# HC-NBIOT_Single_lamp_controller-V1_1.net
KiCad netlist of a schematic drawn in Altium Designer
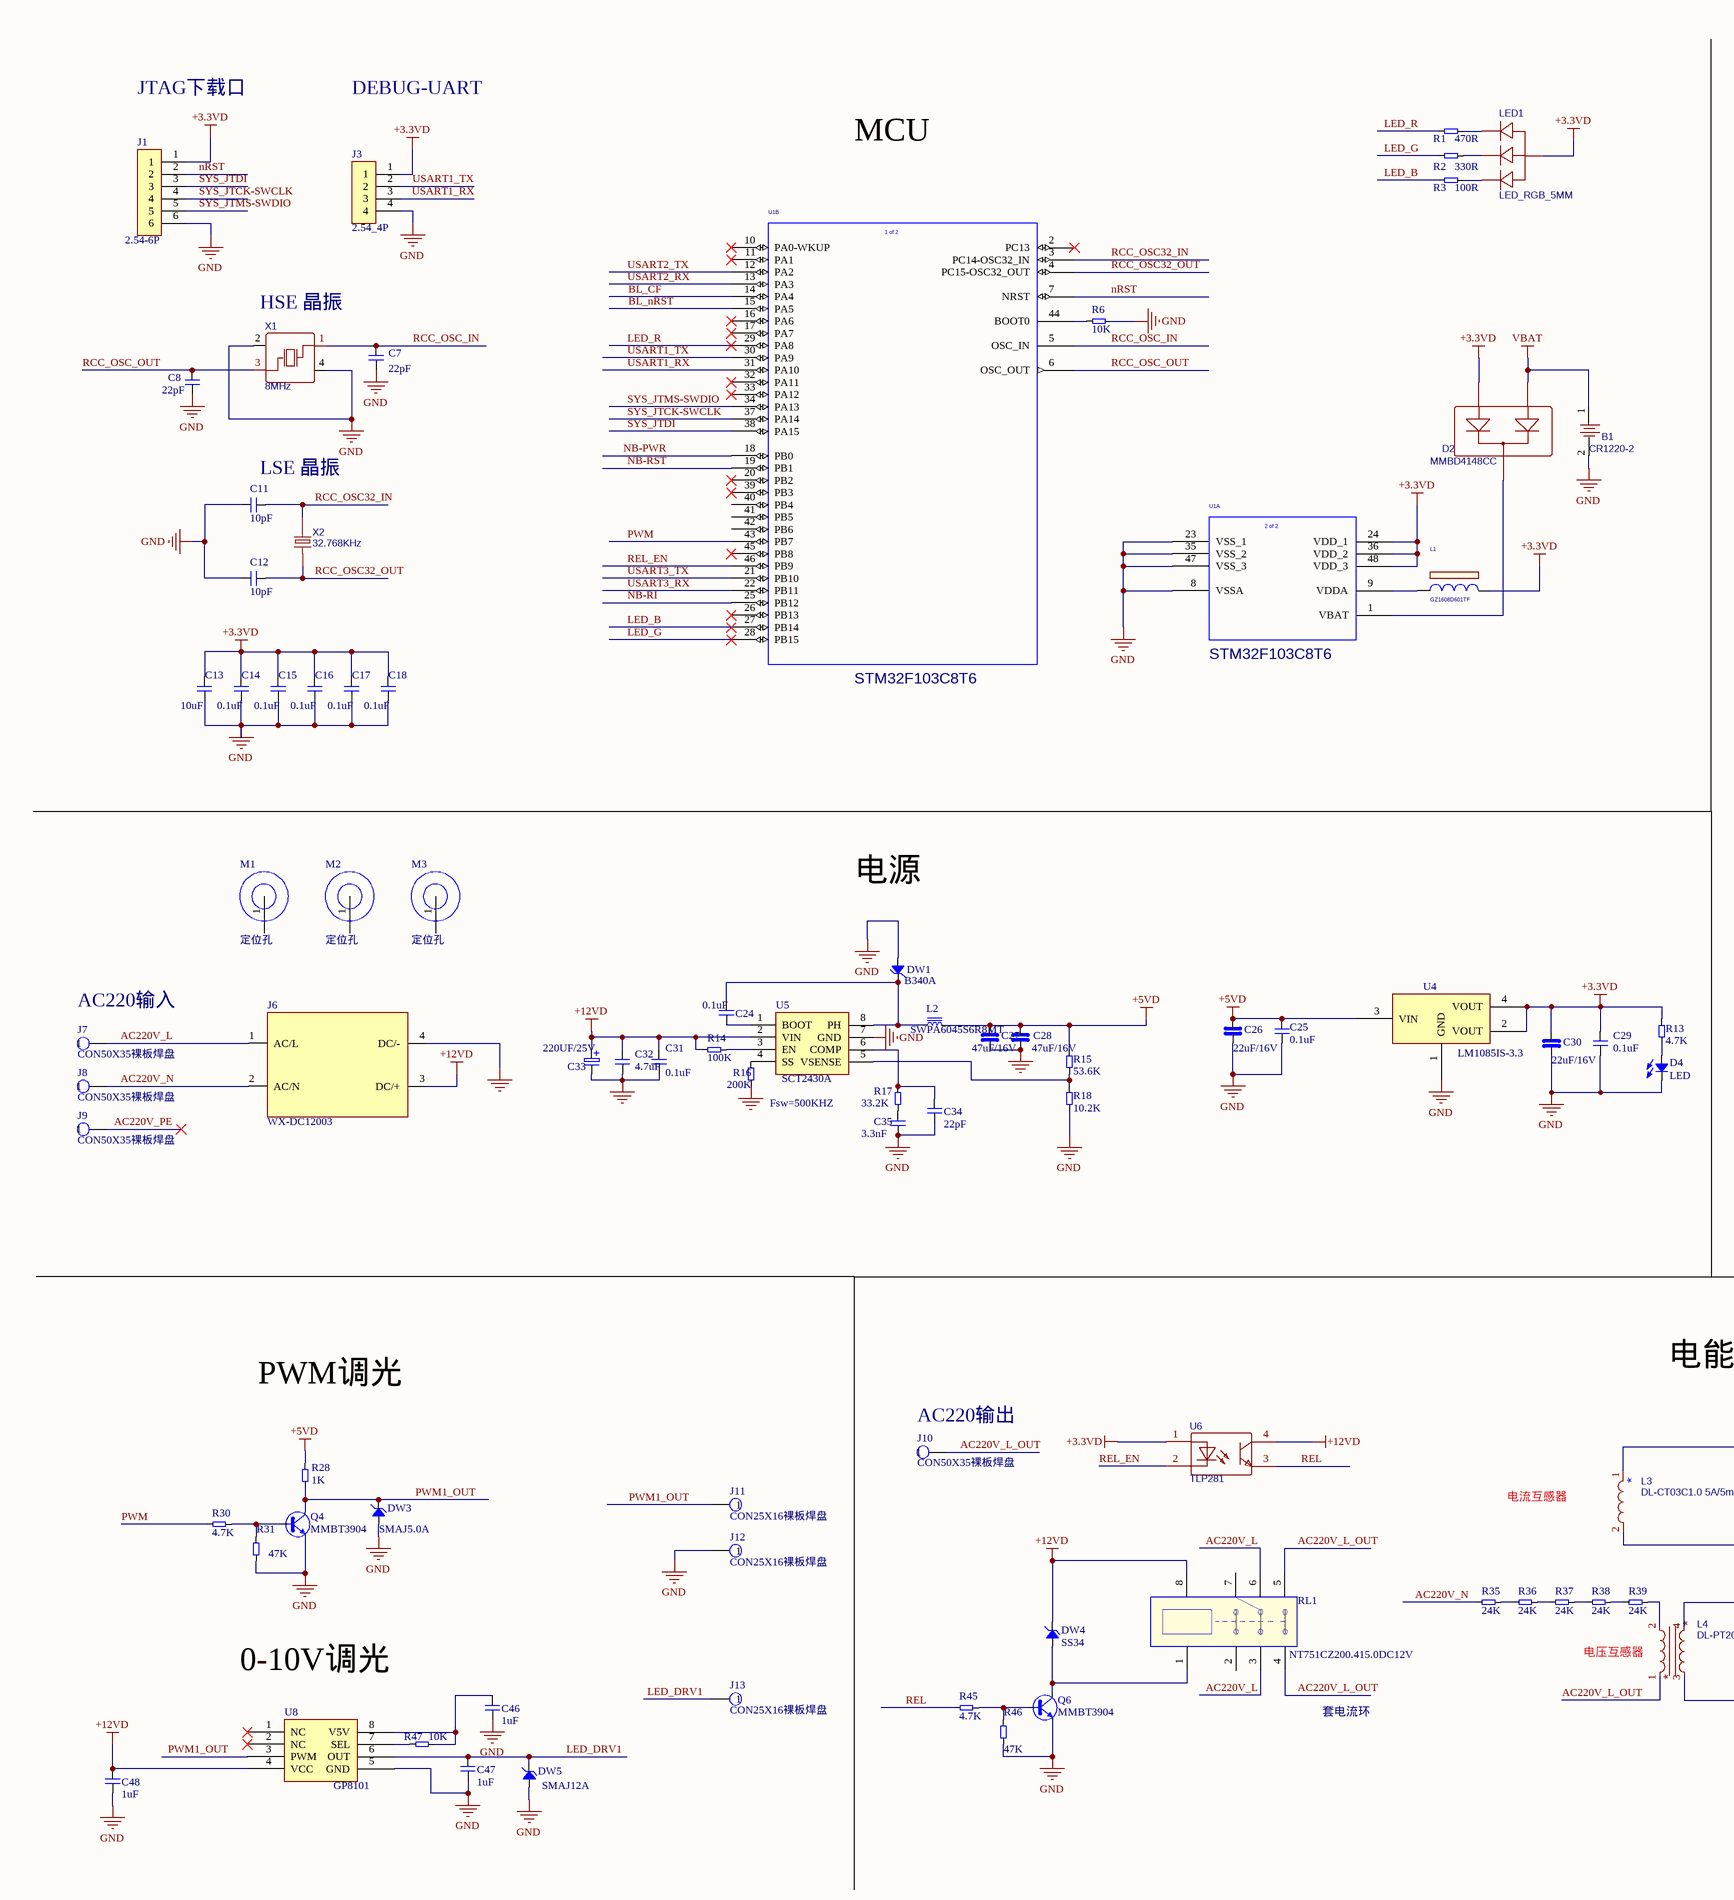
[diagram p0: HC-NBIOT_Single_lamp_controller-V1.1.SchDoc, left]
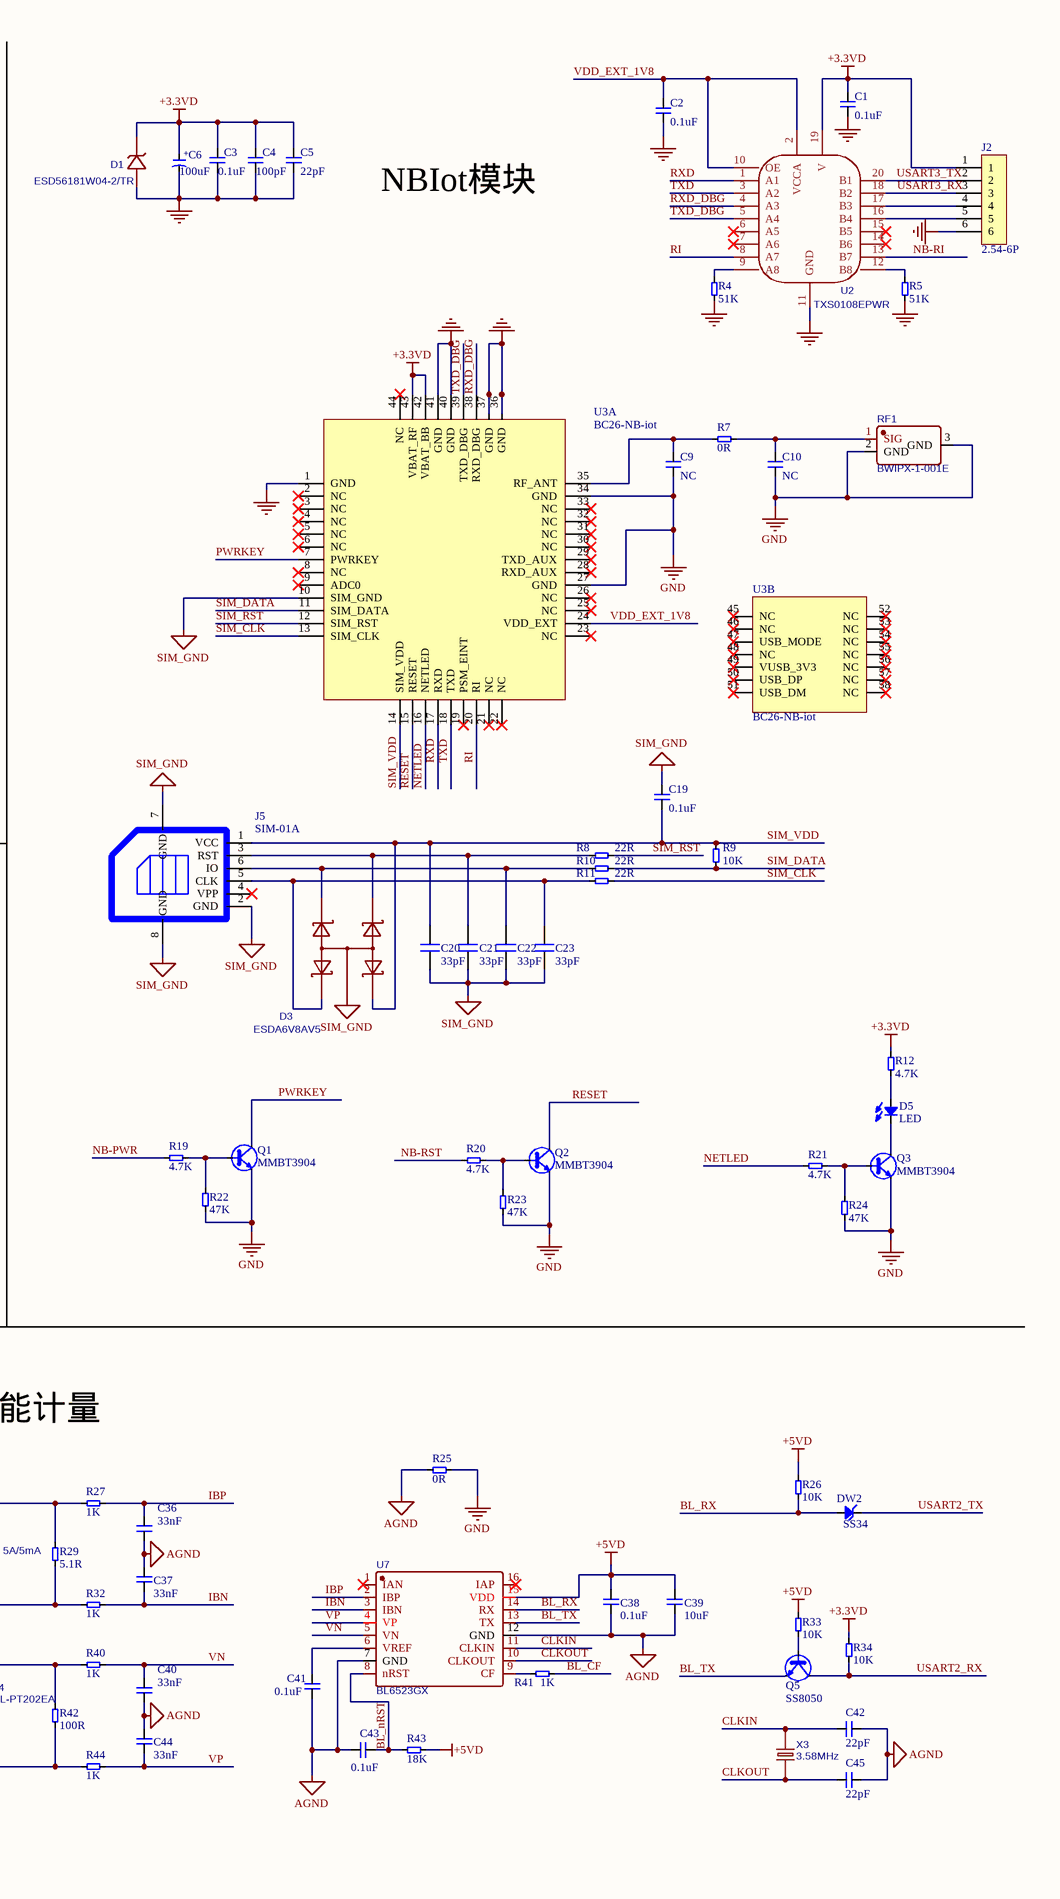
[diagram p1: HC-NBIOT_Single_lamp_controller-V1.1.SchDoc, right]

(export (version "E")
  (design (tool "Eeschema 10.0.6"))
  (components
    (comp (ref "B1")
      (value "CR1220-2")
      (footprint "BAT-SMD_CR1220-2")
      (fields (field (name "BOM_SUPPLIER PART") "C70381"))
      (libsource (lib "czc") (part "CR1220-2"))
    )
    (comp (ref "C1")
      (value "0.1uF")
      (footprint "0603C")
      (description "电容")
      (libsource (lib "DOFAR_AD_LIB") (part "电容"))
    )
    (comp (ref "C2")
      (value "0.1uF")
      (footprint "0603C")
      (description "电容")
      (libsource (lib "DOFAR_AD_LIB") (part "电容"))
    )
    (comp (ref "C3")
      (value "0.1uF")
      (footprint "0603C")
      (description "电容")
      (libsource (lib "DOFAR_AD_LIB") (part "电容"))
    )
    (comp (ref "C4")
      (value "100pF")
      (footprint "0603C")
      (description "电容")
      (libsource (lib "DOFAR_AD_LIB") (part "电容"))
    )
    (comp (ref "C5")
      (value "22pF")
      (footprint "0603C")
      (description "电容")
      (libsource (lib "DOFAR_AD_LIB") (part "电容"))
    )
    (comp (ref "C6")
      (value "100uF")
      (footprint "CAP-SMD_L3.5-W2.8")
      (description "电解电容")
      (libsource (lib "czc") (part "Capacitor"))
    )
    (comp (ref "C7")
      (value "22pF")
      (footprint "0603C")
      (description "电容")
      (libsource (lib "DOFAR_AD_LIB") (part "电容"))
    )
    (comp (ref "C8")
      (value "22pF")
      (footprint "0603C")
      (description "电容")
      (libsource (lib "DOFAR_AD_LIB") (part "电容"))
    )
    (comp (ref "C9")
      (value "NC")
      (footprint "0603C")
      (description "电容")
      (libsource (lib "DOFAR_AD_LIB") (part "电容"))
    )
    (comp (ref "C10")
      (value "NC")
      (footprint "0603C")
      (description "电容")
      (libsource (lib "DOFAR_AD_LIB") (part "电容"))
    )
    (comp (ref "C11")
      (value "10pF")
      (footprint "0603C")
      (description "电容")
      (libsource (lib "DOFAR_AD_LIB") (part "电容"))
    )
    (comp (ref "C12")
      (value "10pF")
      (footprint "0603C")
      (description "电容")
      (libsource (lib "DOFAR_AD_LIB") (part "电容"))
    )
    (comp (ref "C13")
      (value "10uF")
      (footprint "1206C")
      (description "电容")
      (libsource (lib "DOFAR_AD_LIB") (part "电容"))
    )
    (comp (ref "C14")
      (value "0.1uF")
      (footprint "0603C")
      (description "电容")
      (libsource (lib "DOFAR_AD_LIB") (part "电容"))
    )
    (comp (ref "C15")
      (value "0.1uF")
      (footprint "0603C")
      (description "电容")
      (libsource (lib "DOFAR_AD_LIB") (part "电容"))
    )
    (comp (ref "C16")
      (value "0.1uF")
      (footprint "0603C")
      (description "电容")
      (libsource (lib "DOFAR_AD_LIB") (part "电容"))
    )
    (comp (ref "C17")
      (value "0.1uF")
      (footprint "0603C")
      (description "电容")
      (libsource (lib "DOFAR_AD_LIB") (part "电容"))
    )
    (comp (ref "C18")
      (value "0.1uF")
      (footprint "0603C")
      (description "电容")
      (libsource (lib "DOFAR_AD_LIB") (part "电容"))
    )
    (comp (ref "C19")
      (value "0.1uF")
      (footprint "0603C")
      (description "电容")
      (libsource (lib "DOFAR_AD_LIB") (part "电容"))
    )
    (comp (ref "C20")
      (value "33pF")
      (footprint "0603C")
      (description "电容")
      (libsource (lib "czc") (part "CAP"))
    )
    (comp (ref "C21")
      (value "33pF")
      (footprint "0603C")
      (description "电容")
      (libsource (lib "czc") (part "CAP"))
    )
    (comp (ref "C22")
      (value "33pF")
      (footprint "0603C")
      (description "电容")
      (libsource (lib "czc") (part "CAP"))
    )
    (comp (ref "C23")
      (value "33pF")
      (footprint "0603C")
      (description "电容")
      (libsource (lib "czc") (part "CAP"))
    )
    (comp (ref "C24")
      (value "0.1uF")
      (footprint "0603C")
      (description "电容")
      (libsource (lib "DOFAR_AD_LIB") (part "电容"))
    )
    (comp (ref "C25")
      (value "0.1uF")
      (footprint "0603C")
      (description "电容")
      (libsource (lib "*") (part "电容"))
    )
    (comp (ref "C26")
      (value "22uF/16V")
      (footprint "1206C")
      (description "多层陶瓷电容")
      (libsource (lib "DF-CBOX-BB") (part "多层陶瓷电容"))
    )
    (comp (ref "C27")
      (value "47uF/16V")
      (footprint "1206C")
      (description "多层陶瓷电容")
      (libsource (lib "DOFAR_AD_LIB") (part "多层陶瓷电容"))
    )
    (comp (ref "C28")
      (value "47uF/16V")
      (footprint "1206C")
      (description "多层陶瓷电容")
      (libsource (lib "DOFAR_AD_LIB") (part "多层陶瓷电容"))
    )
    (comp (ref "C29")
      (value "0.1uF")
      (footprint "0603C")
      (description "电容")
      (libsource (lib "*") (part "电容"))
    )
    (comp (ref "C30")
      (value "22uF/16V")
      (footprint "1206C")
      (description "多层陶瓷电容")
      (libsource (lib "dofar-lib") (part "多层陶瓷电容"))
    )
    (comp (ref "C31")
      (value "0.1uF")
      (footprint "0603C")
      (description "电容")
      (libsource (lib "DOFAR_AD_LIB") (part "电容"))
    )
    (comp (ref "C32")
      (value "4.7uF")
      (footprint "0603C")
      (description "电容")
      (libsource (lib "*") (part "电容"))
    )
    (comp (ref "C33")
      (value "220UF/25V")
      (footprint "RAD-3R8")
      (description "电解电容")
      (libsource (lib "DOFAR_AD_LIB") (part "直插电解电容"))
    )
    (comp (ref "C34")
      (value "22pF")
      (footprint "0603C")
      (description "电容")
      (libsource (lib "DOFAR_AD_LIB") (part "电容"))
    )
    (comp (ref "C35")
      (value "3.3nF")
      (footprint "0603C")
      (description "电容")
      (libsource (lib "DOFAR_AD_LIB") (part "电容"))
    )
    (comp (ref "C36")
      (value "33nF")
      (footprint "0603C")
      (description "电容")
      (libsource (lib "DOFAR_AD_LIB") (part "电容"))
    )
    (comp (ref "C37")
      (value "33nF")
      (footprint "0603C")
      (description "电容")
      (libsource (lib "DOFAR_AD_LIB") (part "电容"))
    )
    (comp (ref "C38")
      (value "0.1uF")
      (footprint "0603C")
      (description "电容")
      (libsource (lib "DOFAR_AD_LIB") (part "电容"))
    )
    (comp (ref "C39")
      (value "10uF")
      (footprint "1206C")
      (description "电容")
      (libsource (lib "DOFAR_AD_LIB") (part "电容"))
    )
    (comp (ref "C40")
      (value "33nF")
      (footprint "0603C")
      (description "电容")
      (libsource (lib "DOFAR_AD_LIB") (part "电容"))
    )
    (comp (ref "C41")
      (value "0.1uF")
      (footprint "0603C")
      (description "电容")
      (libsource (lib "DOFAR_AD_LIB") (part "电容"))
    )
    (comp (ref "C42")
      (value "22pF")
      (footprint "0603C")
      (description "电容")
      (libsource (lib "DOFAR_AD_LIB") (part "电容"))
    )
    (comp (ref "C43")
      (value "0.1uF")
      (footprint "0603C")
      (description "电容")
      (libsource (lib "DOFAR_AD_LIB") (part "电容"))
    )
    (comp (ref "C44")
      (value "33nF")
      (footprint "0603C")
      (description "电容")
      (libsource (lib "DOFAR_AD_LIB") (part "电容"))
    )
    (comp (ref "C45")
      (value "22pF")
      (footprint "0603C")
      (description "电容")
      (libsource (lib "DOFAR_AD_LIB") (part "电容"))
    )
    (comp (ref "C46")
      (value "1uF")
      (footprint "0603C")
      (description "电容")
      (libsource (lib "DF-CBOX-MB_V1.0") (part "电容"))
    )
    (comp (ref "C47")
      (value "1uF")
      (footprint "0603C")
      (description "电容")
      (libsource (lib "DF-CBOX-MB_V1.0") (part "电容"))
    )
    (comp (ref "C48")
      (value "1uF")
      (footprint "0603C")
      (description "电容")
      (libsource (lib "DF-CBOX-MB_V1.0") (part "电容"))
    )
    (comp (ref "D1")
      (value "ESD56181W04-2/TR")
      (footprint "ESD56181W04")
      (fields (field (name "BOM_SUPPLIER PART") "C910982") (field (name "CONTRIBUTOR") "LCSC"))
      (libsource (lib "czc") (part "TVS二极管"))
    )
    (comp (ref "D2")
      (value "MMBD4148CC")
      (footprint "SOT-23-3")
      (fields (field (name "BOM_SUPPLIER PART") "C8595"))
      (libsource (lib "czc") (part "MMBD4148CC"))
    )
    (comp (ref "D3")
      (value "ESDA6V8AV5")
      (footprint "SOT-553_ESDA6V8AV5")
      (fields (field (name "BOM_SUPPLIER PART") "C268741") (field (name "CONTRIBUTOR") "LCSC"))
      (libsource (lib "czc") (part "ESDA6V8AV5"))
    )
    (comp (ref "D4") (value "LED") (footprint "LED0603") (libsource (lib "czc") (part "发光二极管")))
    (comp (ref "D5") (value "LED") (footprint "LED0603") (libsource (lib "czc") (part "发光二极管")))
    (comp (ref "DW1") (value "B340A") (footprint "SMB") (libsource (lib "DOFAR_AD_LIB") (part "肖特基二极管")))
    (comp (ref "DW2") (value "SS34") (footprint "SMA") (libsource (lib "DOFAR_AD_LIB") (part "肖特基二极管")))
    (comp (ref "DW3") (value "SMAJ5.0A") (footprint "SMA") (libsource (lib "TIMOR_LIB") (part "肖特基二极管")))
    (comp (ref "DW4") (value "SS34") (footprint "SMA") (libsource (lib "TIMOR_LIB") (part "肖特基二极管")))
    (comp (ref "DW5") (value "SMAJ12A") (footprint "SMA") (libsource (lib "TIMOR_LIB") (part "肖特基二极管")))
    (comp (ref "J1") (value "2.54-6P") (footprint "2.54-6P") (libsource (lib "czc") (part "PIN_6P")))
    (comp (ref "J2") (value "2.54-6P") (footprint "2.54-6P") (libsource (lib "") (part "PIN_6P_1")))
    (comp (ref "J3") (value "2.54_4P") (footprint "2.54-4P") (libsource (lib "czc") (part "PIN_4P")))
    (comp (ref "J5")
      (value "SIM-01A")
      (footprint "SIM-01A")
      (description "SIM卡座")
      (libsource (lib "czc") (part "SIM-01A"))
    )
    (comp (ref "J6")
      (value "WX-DC12003")
      (footprint "WX-DC12003")
      (libsource (lib "czc") (part "WX-DC12003"))
    )
    (comp (ref "J7")
      (value "CON50X35裸板焊盘")
      (footprint "SCREW5030")
      (libsource (lib "DF-CBOX-BB") (part "CON1X1"))
    )
    (comp (ref "J8")
      (value "CON50X35裸板焊盘")
      (footprint "SCREW5030")
      (libsource (lib "DF-CBOX-BB") (part "CON1X1"))
    )
    (comp (ref "J9")
      (value "CON50X35裸板焊盘")
      (footprint "SCREW5030")
      (libsource (lib "DF-CBOX-BB") (part "CON1X1"))
    )
    (comp (ref "J10")
      (value "CON50X35裸板焊盘")
      (footprint "SCREW5030")
      (libsource (lib "DF-CBOX-BB") (part "CON1X1"))
    )
    (comp (ref "J11")
      (value "CON25X16裸板焊盘")
      (footprint "SCREW2516")
      (libsource (lib "DF-CBOX-BB") (part "CON1X1"))
    )
    (comp (ref "J12")
      (value "CON25X16裸板焊盘")
      (footprint "SCREW2516")
      (libsource (lib "DF-CBOX-BB") (part "CON1X1"))
    )
    (comp (ref "J13")
      (value "CON25X16裸板焊盘")
      (footprint "SCREW2516")
      (libsource (lib "DF-CBOX-BB") (part "CON1X1"))
    )
    (comp (ref "L1")
      (value "GZ1608D601TF")
      (footprint "0603L")
      (description "IND FER BEAD 120 OHM@100MHZ 0.5A 25% 0402")
      (fields (field (name "TOLERANCE") "25%"))
      (libsource (lib "czc") (part "INDUCTOR_FERRITE"))
    )
    (comp (ref "L2")
      (value "SWPA6045S6R8MT")
      (footprint "SDRH6D45")
      (libsource (lib "DOFAR_AD_LIB") (part "功率电感"))
    )
    (comp (ref "L3")
      (value "DL-CT03C1.0 5A/5mA")
      (footprint "DL-CT03C1.0 5A/5mA")
      (fields (field (name "BOM_MANUFACTURER PART") "ZMCT102") (field (name "BOM_SUPPLIER PART") "C84213"))
      (libsource (lib "czc") (part "DL-CT03C1.0 5A/5mA"))
    )
    (comp (ref "L4")
      (value "DL-PT202EA")
      (footprint "DL-PT202EA")
      (fields (field (name "BOM_MANUFACTURER PART") "ZMPT107-1") (field (name "BOM_SUPPLIER PART") "C125191"))
      (libsource (lib "czc") (part "DL-PT202EA"))
    )
    (comp (ref "LED1")
      (value "LED_RGB_5MM")
      (footprint "LED_RGB_5MM")
      (fields
        (field (name "BOM_SUPPLIER PART") "C417349")
        (field (name "BOM_MANUFACTURER PART") "MHLA5319URGBDWT")
        (field (name "CONTRIBUTOR") "LCSC")
      )
      (libsource (lib "czc") (part "LED_REB_5MM"))
    )
    (comp (ref "M1") (value "定位孔") (footprint "SCREW7035") (libsource (lib "typ-lib") (part "定位孔")))
    (comp (ref "M2") (value "定位孔") (footprint "SCREW7035") (libsource (lib "typ-lib") (part "定位孔")))
    (comp (ref "M3") (value "定位孔") (footprint "SCREW7035") (libsource (lib "typ-lib") (part "定位孔")))
    (comp (ref "Q1") (value "MMBT3904") (footprint "SOT-23") (libsource (lib "dofar-lib") (part "MMBT3904")))
    (comp (ref "Q2") (value "MMBT3904") (footprint "SOT-23") (libsource (lib "dofar-lib") (part "MMBT3904")))
    (comp (ref "Q3") (value "MMBT3904") (footprint "SOT-23") (libsource (lib "dofar-lib") (part "MMBT3904")))
    (comp (ref "Q4") (value "MMBT3904") (footprint "SOT-23") (libsource (lib "dofar-lib") (part "MMBT3904")))
    (comp (ref "Q5") (value "SS8050") (footprint "SOT-23") (libsource (lib "dofar-lib") (part "MMBT3904")))
    (comp (ref "Q6") (value "MMBT3904") (footprint "SOT-23") (libsource (lib "dofar-lib") (part "MMBT3904")))
    (comp (ref "R1") (value "470R") (footprint "0603R") (description "电阻") (libsource (lib "*") (part "电阻")))
    (comp (ref "R2") (value "330R") (footprint "0603R") (description "电阻") (libsource (lib "*") (part "电阻")))
    (comp (ref "R3") (value "100R") (footprint "0603R") (description "电阻") (libsource (lib "*") (part "电阻")))
    (comp (ref "R4")
      (value "51K")
      (footprint "0603R")
      (description "电阻")
      (libsource (lib "DOFAR_AD_LIB") (part "电阻"))
    )
    (comp (ref "R5")
      (value "51K")
      (footprint "0603R")
      (description "电阻")
      (libsource (lib "DOFAR_AD_LIB") (part "电阻"))
    )
    (comp (ref "R6") (value "10K") (footprint "0603R") (description "电阻") (libsource (lib "*") (part "电阻")))
    (comp (ref "R7")
      (value "0R")
      (footprint "0603R")
      (description "电阻")
      (libsource (lib "DOFAR_AD_LIB") (part "电阻"))
    )
    (comp (ref "R8")
      (value "22R")
      (footprint "0603R")
      (description "电阻")
      (libsource (lib "DOFAR_AD_LIB") (part "电阻"))
    )
    (comp (ref "R9")
      (value "10K")
      (footprint "0603R")
      (description "电阻")
      (libsource (lib "DOFAR_AD_LIB") (part "电阻"))
    )
    (comp (ref "R10")
      (value "22R")
      (footprint "0603R")
      (description "电阻")
      (libsource (lib "DOFAR_AD_LIB") (part "电阻"))
    )
    (comp (ref "R11")
      (value "22R")
      (footprint "0603R")
      (description "电阻")
      (libsource (lib "DOFAR_AD_LIB") (part "电阻"))
    )
    (comp (ref "R12")
      (value "4.7K")
      (footprint "0603R")
      (description "电阻")
      (libsource (lib "LOUB-AD") (part "电阻"))
    )
    (comp (ref "R13") (value "4.7K") (footprint "0603R") (description "电阻") (libsource (lib "*") (part "电阻")))
    (comp (ref "R14")
      (value "100K")
      (footprint "0603R")
      (description "电阻")
      (libsource (lib "DOFAR_AD_LIB") (part "电阻"))
    )
    (comp (ref "R15")
      (value "53.6K")
      (footprint "0603R")
      (description "电阻")
      (libsource (lib "DOFAR_AD_LIB") (part "电阻"))
    )
    (comp (ref "R16")
      (value "200K")
      (footprint "0603R")
      (description "电阻")
      (libsource (lib "DOFAR_AD_LIB") (part "电阻"))
    )
    (comp (ref "R17")
      (value "33.2K")
      (footprint "0603R")
      (description "电阻")
      (libsource (lib "*") (part "电阻"))
    )
    (comp (ref "R18")
      (value "10.2K")
      (footprint "0603R")
      (description "电阻")
      (libsource (lib "DOFAR_AD_LIB") (part "电阻"))
    )
    (comp (ref "R19")
      (value "4.7K")
      (footprint "0603R")
      (description "电阻")
      (libsource (lib "LOUB-AD") (part "电阻"))
    )
    (comp (ref "R20")
      (value "4.7K")
      (footprint "0603R")
      (description "电阻")
      (libsource (lib "LOUB-AD") (part "电阻"))
    )
    (comp (ref "R21")
      (value "4.7K")
      (footprint "0603R")
      (description "电阻")
      (libsource (lib "LOUB-AD") (part "电阻"))
    )
    (comp (ref "R22")
      (value "47K")
      (footprint "0603R")
      (description "电阻")
      (libsource (lib "LOUB-AD") (part "电阻"))
    )
    (comp (ref "R23")
      (value "47K")
      (footprint "0603R")
      (description "电阻")
      (libsource (lib "LOUB-AD") (part "电阻"))
    )
    (comp (ref "R24")
      (value "47K")
      (footprint "0603R")
      (description "电阻")
      (libsource (lib "LOUB-AD") (part "电阻"))
    )
    (comp (ref "R25")
      (value "0R")
      (footprint "0603R")
      (description "电阻")
      (libsource (lib "LOUB-AD") (part "电阻"))
    )
    (comp (ref "R26")
      (value "10K")
      (footprint "0603R")
      (description "电阻")
      (libsource (lib "LOUB-AD") (part "电阻"))
    )
    (comp (ref "R27")
      (value "1K")
      (footprint "0603R")
      (description "电阻")
      (libsource (lib "LOUB-AD") (part "电阻"))
    )
    (comp (ref "R28")
      (value "1K")
      (footprint "0603R")
      (description "电阻")
      (libsource (lib "dofar-lib") (part "电阻"))
    )
    (comp (ref "R29")
      (value "5.1R")
      (footprint "0603R")
      (description "电阻")
      (libsource (lib "LOUB-AD") (part "电阻"))
    )
    (comp (ref "R30")
      (value "4.7K")
      (footprint "0603R")
      (description "电阻")
      (libsource (lib "DOFAR_AD_LIB") (part "电阻"))
    )
    (comp (ref "R31")
      (value "47K")
      (footprint "0603R")
      (description "电阻")
      (libsource (lib "LOUB-AD") (part "电阻"))
    )
    (comp (ref "R32")
      (value "1K")
      (footprint "0603R")
      (description "电阻")
      (libsource (lib "LOUB-AD") (part "电阻"))
    )
    (comp (ref "R33")
      (value "10K")
      (footprint "0603R")
      (description "电阻")
      (libsource (lib "LOUB-AD") (part "电阻"))
    )
    (comp (ref "R34")
      (value "10K")
      (footprint "0603R")
      (description "电阻")
      (libsource (lib "LOUB-AD") (part "电阻"))
    )
    (comp (ref "R35")
      (value "24K")
      (footprint "0603R")
      (description "电阻")
      (libsource (lib "LOUB-AD") (part "电阻"))
    )
    (comp (ref "R36")
      (value "24K")
      (footprint "0603R")
      (description "电阻")
      (libsource (lib "LOUB-AD") (part "电阻"))
    )
    (comp (ref "R37")
      (value "24K")
      (footprint "0603R")
      (description "电阻")
      (libsource (lib "LOUB-AD") (part "电阻"))
    )
    (comp (ref "R38")
      (value "24K")
      (footprint "0603R")
      (description "电阻")
      (libsource (lib "LOUB-AD") (part "电阻"))
    )
    (comp (ref "R39")
      (value "24K")
      (footprint "0603R")
      (description "电阻")
      (libsource (lib "LOUB-AD") (part "电阻"))
    )
    (comp (ref "R40")
      (value "1K")
      (footprint "0603R")
      (description "电阻")
      (libsource (lib "LOUB-AD") (part "电阻"))
    )
    (comp (ref "R41")
      (value "1K")
      (footprint "0603R")
      (description "电阻")
      (libsource (lib "LOUB-AD") (part "电阻"))
    )
    (comp (ref "R42")
      (value "100R")
      (footprint "0603R")
      (description "电阻")
      (libsource (lib "LOUB-AD") (part "电阻"))
    )
    (comp (ref "R43")
      (value "18K")
      (footprint "0603R")
      (description "电阻")
      (libsource (lib "LOUB-AD") (part "电阻"))
    )
    (comp (ref "R44")
      (value "1K")
      (footprint "0603R")
      (description "电阻")
      (libsource (lib "LOUB-AD") (part "电阻"))
    )
    (comp (ref "R45")
      (value "4.7K")
      (footprint "0603R")
      (description "电阻")
      (libsource (lib "LOUB-AD") (part "电阻"))
    )
    (comp (ref "R46")
      (value "47K")
      (footprint "0603R")
      (description "电阻")
      (libsource (lib "LOUB-AD") (part "电阻"))
    )
    (comp (ref "R47")
      (value "10K")
      (footprint "0603R")
      (description "电阻")
      (libsource (lib "dofar-lib") (part "电阻"))
    )
    (comp (ref "RF1")
      (value "BWIPX-1-001E")
      (footprint "IPEX一代天线座")
      (fields (field (name "BOM_SUPPLIER PART") "C496552") (field (name "CONTRIBUTOR") "LCSC"))
      (libsource (lib "czc") (part "IPEX一代天线座"))
    )
    (comp (ref "RL1")
      (value "NT751CZ200.415.0DC12V")
      (footprint "G2R-2-24VDC")
      (description "Relay")
      (fields (field (name "PUBLISHER") "Altium Limited"))
      (libsource (lib "TIMOR-SCH") (part "Relay-SPDT"))
    )
    (comp (ref "U1")
      (value "STM32F103C8T6")
      (footprint "STM32F103C8T6")
      (fields
        (field (name "MANUFACTURER_PART_NUMBER") "stm32f103cxt2")
        (field (name "< VALUE >") "STM32F103C8T6")
        (field (name "COPYRIGHT") "Copyright (C) 2016 Accelerated Designs. All rights reserved")
      )
      (libsource (lib "czc") (part "STM32F103C8T6"))
    )
    (comp (ref "U2")
      (value "TXS0108EPWR")
      (footprint "TXS0108EPWR")
      (fields (field (name "BOM_SUPPLIER PART") "C17206"))
      (libsource (lib "czc") (part "TXS0108EPWR"))
    )
    (comp (ref "U3") (value "BC26-NB-iot") (footprint "BC26") (libsource (lib "czc") (part "BC26")))
    (comp (ref "U4")
      (value "LM1085IS-3.3")
      (footprint "TO-263-3")
      (description "3A Low Dropout Positive Regulators")
      (libsource (lib "*") (part "LM1085"))
    )
    (comp (ref "U5")
      (value "SCT2430A")
      (footprint "SOIC8EP-1,27")
      (libsource (lib "DOFAR_AD_LIB") (part "TPS54331"))
    )
    (comp (ref "U6")
      (value "TLP281")
      (footprint "SMD-4")
      (fields (field (name "BOM_SUPPLIER PART") "C433437") (field (name "CONTRIBUTOR") "LCSC"))
      (libsource (lib "czc") (part "TLP281"))
    )
    (comp (ref "U7")
      (value "BL6523GX")
      (footprint "SOP-16_BL6523GX")
      (fields (field (name "BOM_SUPPLIER PART") "C213392") (field (name "CONTRIBUTOR") "LCSC"))
      (libsource (lib "czc") (part "BL6523GX"))
    )
    (comp (ref "U8")
      (value "GP8101")
      (footprint "SOIC8-1,27")
      (description "PWM 2 ANALOG")
      (libsource (lib "TIMOR-SCH") (part "GP8101"))
    )
    (comp (ref "X1")
      (value "8MHz")
      (footprint "OSC-SMD_4P-25M")
      (fields
        (field (name "BOM_MANUFACTURER PART") "X1E0000210352000G")
        (field (name "BOM_SUPPLIER PART") "C91738")
      )
      (libsource (lib "czc") (part "TSX-3225 25MHz 20pF 10ppm"))
    )
    (comp (ref "X2")
      (value "32.768KHz")
      (footprint "OSC-SMD_2P-32.768K")
      (fields
        (field (name "BOM_MANUFACTURER PART") "SC-32S32.768kHz20PPM7pF")
        (field (name "BOM_SUPPLIER PART") "C97604")
      )
      (libsource (lib "czc") (part "32.768kHz 20PPM 7pF"))
    )
    (comp (ref "X3")
      (value "3.58MHz")
      (footprint "HC-49SMD_3.58M")
      (fields
        (field (name "BOM_MANUFACTURER PART") "SC-32S32.768kHz20PPM7pF")
        (field (name "BOM_SUPPLIER PART") "C97604")
      )
      (libsource (lib "czc") (part "32.768kHz 20PPM 7pF"))
    )
  )
  (nets
    (net (code "1") (name "+3.3VD") (class "Default")
      (node (ref "C1") (pin "1") (pintype "passive"))
      (node (ref "C13") (pin "2") (pintype "passive"))
      (node (ref "C14") (pin "2") (pintype "passive"))
      (node (ref "C15") (pin "2") (pintype "passive"))
      (node (ref "C16") (pin "2") (pintype "passive"))
      (node (ref "C17") (pin "2") (pintype "passive"))
      (node (ref "C18") (pin "2") (pintype "passive"))
      (node (ref "C29") (pin "2") (pintype "passive"))
      (node (ref "C3") (pin "1") (pintype "passive"))
      (node (ref "C30") (pin "1") (pintype "passive"))
      (node (ref "C4") (pin "1") (pintype "passive"))
      (node (ref "C5") (pin "1") (pintype "passive"))
      (node (ref "C6") (pin "1") (pinfunction "1_1") (pintype "passive"))
      (node (ref "D1") (pin "1") (pinfunction "K_1") (pintype "passive"))
      (node (ref "D2") (pin "2") (pinfunction "2_2") (pintype "passive"))
      (node (ref "J1") (pin "1") (pinfunction "1_1") (pintype "passive"))
      (node (ref "J2") (pin "1") (pinfunction "1_1") (pintype "passive"))
      (node (ref "J3") (pin "1") (pinfunction "1_1") (pintype "passive"))
      (node (ref "L1") (pin "2") (pinfunction "2_2") (pintype "passive"))
      (node (ref "LED1") (pin "2") (pinfunction "+_2") (pintype "passive"))
      (node (ref "R12") (pin "2") (pintype "passive"))
      (node (ref "R13") (pin "1") (pintype "passive"))
      (node (ref "R34") (pin "1") (pintype "passive"))
      (node (ref "U1") (pin "24") (pinfunction "VDD_1_24") (pintype "power_in"))
      (node (ref "U1") (pin "36") (pinfunction "VDD_2_36") (pintype "power_in"))
      (node (ref "U1") (pin "48") (pinfunction "VDD_3_48") (pintype "power_in"))
      (node (ref "U2") (pin "19") (pinfunction "V_19") (pintype "passive"))
      (node (ref "U3") (pin "42") (pinfunction "VBAT_BB_42") (pintype "passive"))
      (node (ref "U3") (pin "43") (pinfunction "VBAT_RF_43") (pintype "passive"))
      (node (ref "U4") (pin "2") (pinfunction "VOUT_2") (pintype "passive"))
      (node (ref "U4") (pin "4") (pinfunction "VOUT_4") (pintype "passive"))
      (node (ref "U6") (pin "1") (pinfunction "1_1") (pintype "passive"))
    )
    (net (code "2") (name "+5VD") (class "Default")
      (node (ref "C25") (pin "1") (pintype "passive"))
      (node (ref "C26") (pin "1") (pintype "passive"))
      (node (ref "C27") (pin "1") (pintype "passive"))
      (node (ref "C28") (pin "1") (pintype "passive"))
      (node (ref "C38") (pin "2") (pintype "passive"))
      (node (ref "C39") (pin "2") (pintype "passive"))
      (node (ref "L2") (pin "2") (pintype "passive"))
      (node (ref "R15") (pin "2") (pintype "passive"))
      (node (ref "R26") (pin "1") (pintype "passive"))
      (node (ref "R28") (pin "2") (pintype "passive"))
      (node (ref "R33") (pin "1") (pintype "passive"))
      (node (ref "R43") (pin "1") (pintype "passive"))
      (node (ref "U4") (pin "3") (pinfunction "VIN_3") (pintype "passive"))
      (node (ref "U7") (pin "15") (pinfunction "VDD_15") (pintype "passive"))
    )
    (net (code "3") (name "+12VD") (class "Default")
      (node (ref "C31") (pin "2") (pintype "passive"))
      (node (ref "C32") (pin "2") (pintype "passive"))
      (node (ref "C33") (pin "1") (pintype "passive"))
      (node (ref "C48") (pin "2") (pintype "passive"))
      (node (ref "DW4") (pin "K") (pintype "passive"))
      (node (ref "J6") (pin "3") (pinfunction "DC/+_3") (pintype "passive"))
      (node (ref "R14") (pin "2") (pintype "passive"))
      (node (ref "RL1") (pin "8") (pinfunction "8_8") (pintype "passive"))
      (node (ref "U5") (pin "2") (pinfunction "VIN_2") (pintype "passive"))
      (node (ref "U6") (pin "4") (pinfunction "4_4") (pintype "passive"))
      (node (ref "U8") (pin "4") (pinfunction "VCC_4") (pintype "passive"))
    )
    (net (code "4") (name "/AC220V_L") (class "Default")
      (node (ref "J6") (pin "1") (pinfunction "AC/L_1") (pintype "passive"))
      (node (ref "J7") (pin "1") (pinfunction "1_1") (pintype "passive"))
      (node (ref "RL1") (pin "3") (pinfunction "3_3") (pintype "passive"))
      (node (ref "RL1") (pin "6") (pinfunction "6_6") (pintype "passive"))
    )
    (net (code "5") (name "/AC220V_L_OUT") (class "Default")
      (node (ref "J10") (pin "1") (pinfunction "1_1") (pintype "passive"))
      (node (ref "L4") (pin "1") (pinfunction "1_1") (pintype "passive"))
      (node (ref "RL1") (pin "4") (pinfunction "4_4") (pintype "passive"))
      (node (ref "RL1") (pin "5") (pinfunction "5_5") (pintype "passive"))
    )
    (net (code "6") (name "/AC220V_N") (class "Default")
      (node (ref "J6") (pin "2") (pinfunction "AC/N_2") (pintype "passive"))
      (node (ref "J8") (pin "1") (pinfunction "1_1") (pintype "passive"))
      (node (ref "R35") (pin "2") (pintype "passive"))
    )
    (net (code "7") (name "/AC220V_PE") (class "Default")
      (node (ref "J9") (pin "1") (pinfunction "1_1") (pintype "passive+no_connect"))
    )
    (net (code "8") (name "/BL_CF") (class "Default")
      (node (ref "R41") (pin "2") (pintype "passive"))
      (node (ref "U1") (pin "14") (pinfunction "PA4_14") (pintype "bidirectional"))
    )
    (net (code "9") (name "/BL_RX") (class "Default")
      (node (ref "DW2") (pin "A") (pintype "passive"))
      (node (ref "R26") (pin "2") (pintype "passive"))
      (node (ref "U7") (pin "14") (pinfunction "RX_14") (pintype "passive"))
    )
    (net (code "10") (name "/BL_TX") (class "Default")
      (node (ref "Q5") (pin "2") (pintype "passive"))
      (node (ref "U7") (pin "13") (pinfunction "TX_13") (pintype "passive"))
    )
    (net (code "11") (name "/BL_nRST") (class "Default")
      (node (ref "C43") (pin "1") (pintype "passive"))
      (node (ref "R43") (pin "2") (pintype "passive"))
      (node (ref "U1") (pin "15") (pinfunction "PA5_15") (pintype "bidirectional"))
      (node (ref "U7") (pin "8") (pinfunction "nRST_8") (pintype "passive"))
    )
    (net (code "12") (name "/CLKIN") (class "Default")
      (node (ref "C42") (pin "2") (pintype "passive"))
      (node (ref "U7") (pin "11") (pinfunction "CLKIN_11") (pintype "passive"))
      (node (ref "X3") (pin "2") (pinfunction "2_2") (pintype "passive"))
    )
    (net (code "13") (name "/CLKOUT") (class "Default")
      (node (ref "C45") (pin "2") (pintype "passive"))
      (node (ref "U7") (pin "10") (pinfunction "CLKOUT_10") (pintype "passive"))
      (node (ref "X3") (pin "1") (pinfunction "1_1") (pintype "passive"))
    )
    (net (code "14") (name "/IBN") (class "Default")
      (node (ref "C37") (pin "2") (pintype "passive"))
      (node (ref "R32") (pin "1") (pintype "passive"))
      (node (ref "U7") (pin "3") (pinfunction "IBN_3") (pintype "passive"))
    )
    (net (code "15") (name "/IBP") (class "Default")
      (node (ref "C36") (pin "2") (pintype "passive"))
      (node (ref "R27") (pin "1") (pintype "passive"))
      (node (ref "U7") (pin "2") (pinfunction "IBP_2") (pintype "passive"))
    )
    (net (code "16") (name "/LED_B") (class "Default")
      (node (ref "R3") (pin "2") (pintype "passive"))
      (node (ref "U1") (pin "27") (pinfunction "PB14_27") (pintype "bidirectional"))
    )
    (net (code "17") (name "/LED_DRV1") (class "Default")
      (node (ref "C47") (pin "2") (pintype "passive"))
      (node (ref "DW5") (pin "K") (pintype "passive"))
      (node (ref "J13") (pin "1") (pinfunction "1_1") (pintype "passive"))
      (node (ref "U8") (pin "6") (pinfunction "OUT_6") (pintype "passive"))
    )
    (net (code "18") (name "/LED_G") (class "Default")
      (node (ref "R2") (pin "2") (pintype "passive"))
      (node (ref "U1") (pin "28") (pinfunction "PB15_28") (pintype "bidirectional"))
    )
    (net (code "19") (name "/LED_R") (class "Default")
      (node (ref "R1") (pin "2") (pintype "passive"))
      (node (ref "U1") (pin "29") (pinfunction "PA8_29") (pintype "bidirectional"))
    )
    (net (code "20") (name "/NB-PWR") (class "Default")
      (node (ref "R19") (pin "1") (pintype "passive"))
      (node (ref "U1") (pin "18") (pinfunction "PB0_18") (pintype "bidirectional"))
    )
    (net (code "21") (name "/NB-RI") (class "Default")
      (node (ref "U1") (pin "25") (pinfunction "PB12_25") (pintype "bidirectional"))
      (node (ref "U2") (pin "13") (pinfunction "B7_13") (pintype "passive"))
    )
    (net (code "22") (name "/NB-RST") (class "Default")
      (node (ref "R20") (pin "1") (pintype "passive"))
      (node (ref "U1") (pin "19") (pinfunction "PB1_19") (pintype "bidirectional"))
    )
    (net (code "23") (name "/NETLED") (class "Default")
      (node (ref "R21") (pin "1") (pintype "passive"))
      (node (ref "U3") (pin "16") (pinfunction "NETLED_16") (pintype "passive"))
    )
    (net (code "24") (name "/PWM") (class "Default")
      (node (ref "R30") (pin "2") (pintype "passive"))
      (node (ref "U1") (pin "43") (pinfunction "PB7_43") (pintype "bidirectional"))
    )
    (net (code "25") (name "/PWM1_OUT") (class "Default")
      (node (ref "DW3") (pin "K") (pintype "passive"))
      (node (ref "J11") (pin "1") (pinfunction "1_1") (pintype "passive"))
      (node (ref "Q4") (pin "3") (pintype "passive"))
      (node (ref "R28") (pin "1") (pintype "passive"))
      (node (ref "U8") (pin "3") (pinfunction "PWM_3") (pintype "passive"))
    )
    (net (code "26") (name "/PWRKEY") (class "Default")
      (node (ref "Q1") (pin "3") (pintype "passive"))
      (node (ref "U3") (pin "7") (pinfunction "PWRKEY_7") (pintype "passive"))
    )
    (net (code "27") (name "/RCC_OSC32_IN") (class "Default")
      (node (ref "C11") (pin "1") (pintype "passive"))
      (node (ref "U1") (pin "3") (pinfunction "PC14-OSC32_IN_3") (pintype "bidirectional"))
      (node (ref "X2") (pin "2") (pinfunction "2_2") (pintype "passive"))
    )
    (net (code "28") (name "/RCC_OSC32_OUT") (class "Default")
      (node (ref "C12") (pin "1") (pintype "passive"))
      (node (ref "U1") (pin "4") (pinfunction "PC15-OSC32_OUT_4") (pintype "bidirectional"))
      (node (ref "X2") (pin "1") (pinfunction "1_1") (pintype "passive"))
    )
    (net (code "29") (name "/RCC_OSC_IN") (class "Default")
      (node (ref "C7") (pin "2") (pintype "passive"))
      (node (ref "U1") (pin "5") (pinfunction "OSC_IN_5") (pintype "passive"))
      (node (ref "X1") (pin "1") (pinfunction "OSC1_1") (pintype "passive"))
    )
    (net (code "30") (name "/RCC_OSC_OUT") (class "Default")
      (node (ref "C8") (pin "2") (pintype "passive"))
      (node (ref "U1") (pin "6") (pinfunction "OSC_OUT_6") (pintype "output"))
      (node (ref "X1") (pin "3") (pinfunction "OSC2_3") (pintype "passive"))
    )
    (net (code "31") (name "/REL") (class "Default")
      (node (ref "R45") (pin "1") (pintype "passive"))
      (node (ref "U6") (pin "3") (pinfunction "3_3") (pintype "passive"))
    )
    (net (code "32") (name "/REL_EN") (class "Default")
      (node (ref "U1") (pin "46") (pinfunction "PB9_46") (pintype "bidirectional"))
      (node (ref "U6") (pin "2") (pinfunction "2_2") (pintype "passive"))
    )
    (net (code "33") (name "/RESET") (class "Default")
      (node (ref "Q2") (pin "3") (pintype "passive"))
      (node (ref "U3") (pin "15") (pinfunction "RESET_15") (pintype "passive"))
    )
    (net (code "34") (name "/RI") (class "Default")
      (node (ref "U2") (pin "8") (pinfunction "A7_8") (pintype "passive"))
      (node (ref "U3") (pin "20") (pinfunction "RI_20") (pintype "passive"))
    )
    (net (code "35") (name "/RXD") (class "Default")
      (node (ref "U2") (pin "1") (pinfunction "A1_1") (pintype "passive"))
      (node (ref "U3") (pin "17") (pinfunction "RXD_17") (pintype "passive"))
    )
    (net (code "36") (name "/RXD_DBG") (class "Default")
      (node (ref "U2") (pin "4") (pinfunction "A3_4") (pintype "passive"))
      (node (ref "U3") (pin "38") (pinfunction "RXD_DBG_38") (pintype "passive"))
    )
    (net (code "37") (name "/SIM_CLK") (class "Default")
      (node (ref "R11") (pin "1") (pintype "passive"))
      (node (ref "U3") (pin "13") (pinfunction "SIM_CLK_13") (pintype "passive"))
    )
    (net (code "38") (name "/SIM_DATA") (class "Default")
      (node (ref "R10") (pin "1") (pintype "passive"))
      (node (ref "R9") (pin "2") (pintype "passive"))
      (node (ref "U3") (pin "11") (pinfunction "SIM_DATA_11") (pintype "passive"))
    )
    (net (code "39") (name "/SIM_RST") (class "Default")
      (node (ref "R8") (pin "1") (pintype "passive"))
      (node (ref "U3") (pin "12") (pinfunction "SIM_RST_12") (pintype "passive"))
    )
    (net (code "40") (name "/SIM_VDD") (class "Default")
      (node (ref "C19") (pin "2") (pintype "passive"))
      (node (ref "C20") (pin "2") (pinfunction "2_2") (pintype "passive"))
      (node (ref "D3") (pin "3") (pinfunction "I/O2_3") (pintype "passive"))
      (node (ref "J5") (pin "1") (pinfunction "VCC_1") (pintype "passive"))
      (node (ref "R9") (pin "1") (pintype "passive"))
      (node (ref "U3") (pin "14") (pinfunction "SIM_VDD_14") (pintype "passive"))
    )
    (net (code "41") (name "/SYS_JTCK-SWCLK") (class "Default")
      (node (ref "J1") (pin "4") (pinfunction "4_4") (pintype "passive"))
      (node (ref "U1") (pin "37") (pinfunction "PA14_37") (pintype "bidirectional"))
    )
    (net (code "42") (name "/SYS_JTDI") (class "Default")
      (node (ref "J1") (pin "3") (pinfunction "3_3") (pintype "passive"))
      (node (ref "U1") (pin "38") (pinfunction "PA15_38") (pintype "bidirectional"))
    )
    (net (code "43") (name "/SYS_JTMS-SWDIO") (class "Default")
      (node (ref "J1") (pin "5") (pinfunction "5_5") (pintype "passive"))
      (node (ref "U1") (pin "34") (pinfunction "PA13_34") (pintype "bidirectional"))
    )
    (net (code "44") (name "/TXD") (class "Default")
      (node (ref "U2") (pin "3") (pinfunction "A2_3") (pintype "passive"))
      (node (ref "U3") (pin "18") (pinfunction "TXD_18") (pintype "passive"))
    )
    (net (code "45") (name "/TXD_DBG") (class "Default")
      (node (ref "U2") (pin "5") (pinfunction "A4_5") (pintype "passive"))
      (node (ref "U3") (pin "39") (pinfunction "TXD_DBG_39") (pintype "passive"))
    )
    (net (code "46") (name "/USART1_RX") (class "Default")
      (node (ref "J3") (pin "3") (pinfunction "3_3") (pintype "passive"))
      (node (ref "U1") (pin "31") (pinfunction "PA10_31") (pintype "bidirectional"))
    )
    (net (code "47") (name "/USART1_TX") (class "Default")
      (node (ref "J3") (pin "2") (pinfunction "2_2") (pintype "passive"))
      (node (ref "U1") (pin "30") (pinfunction "PA9_30") (pintype "bidirectional"))
    )
    (net (code "48") (name "/USART2_RX") (class "Default")
      (node (ref "Q5") (pin "3") (pintype "passive"))
      (node (ref "R34") (pin "2") (pintype "passive"))
      (node (ref "U1") (pin "13") (pinfunction "PA3_13") (pintype "bidirectional"))
    )
    (net (code "49") (name "/USART2_TX") (class "Default")
      (node (ref "DW2") (pin "K") (pintype "passive"))
      (node (ref "U1") (pin "12") (pinfunction "PA2_12") (pintype "bidirectional"))
    )
    (net (code "50") (name "/USART3_RX") (class "Default")
      (node (ref "J2") (pin "3") (pinfunction "3_3") (pintype "passive"))
      (node (ref "U1") (pin "22") (pinfunction "PB11_22") (pintype "bidirectional"))
      (node (ref "U2") (pin "18") (pinfunction "B2_18") (pintype "passive"))
    )
    (net (code "51") (name "/USART3_TX") (class "Default")
      (node (ref "J2") (pin "2") (pinfunction "2_2") (pintype "passive"))
      (node (ref "U1") (pin "21") (pinfunction "PB10_21") (pintype "bidirectional"))
      (node (ref "U2") (pin "20") (pinfunction "B1_20") (pintype "passive"))
    )
    (net (code "52") (name "/VDD_EXT_1V8") (class "Default")
      (node (ref "C2") (pin "1") (pintype "passive"))
      (node (ref "U2") (pin "10") (pinfunction "OE_10") (pintype "passive"))
      (node (ref "U2") (pin "2") (pinfunction "VCCA_2") (pintype "passive"))
      (node (ref "U3") (pin "24") (pinfunction "VDD_EXT_24") (pintype "passive"))
    )
    (net (code "53") (name "/VN") (class "Default")
      (node (ref "C40") (pin "2") (pintype "passive"))
      (node (ref "R40") (pin "1") (pintype "passive"))
      (node (ref "U7") (pin "5") (pinfunction "VN_5") (pintype "passive"))
    )
    (net (code "54") (name "/VP") (class "Default")
      (node (ref "C44") (pin "2") (pintype "passive"))
      (node (ref "R44") (pin "1") (pintype "passive"))
      (node (ref "U7") (pin "4") (pinfunction "VP_4") (pintype "passive"))
    )
    (net (code "55") (name "/nRST") (class "Default")
      (node (ref "J1") (pin "2") (pinfunction "2_2") (pintype "passive"))
      (node (ref "U1") (pin "7") (pinfunction "NRST_7") (pintype "bidirectional"))
    )
    (net (code "56") (name "AGND") (class "Default")
      (node (ref "C36") (pin "1") (pintype "passive"))
      (node (ref "C37") (pin "1") (pintype "passive"))
      (node (ref "C38") (pin "1") (pintype "passive"))
      (node (ref "C39") (pin "1") (pintype "passive"))
      (node (ref "C40") (pin "1") (pintype "passive"))
      (node (ref "C41") (pin "1") (pintype "passive"))
      (node (ref "C42") (pin "1") (pintype "passive"))
      (node (ref "C43") (pin "2") (pintype "passive"))
      (node (ref "C44") (pin "1") (pintype "passive"))
      (node (ref "C45") (pin "1") (pintype "passive"))
      (node (ref "R25") (pin "1") (pintype "passive"))
      (node (ref "U7") (pin "12") (pinfunction "GND_12") (pintype "passive"))
      (node (ref "U7") (pin "7") (pinfunction "GND_7") (pintype "passive"))
    )
    (net (code "57") (name "GND") (class "Default")
      (node (ref "B1") (pin "2") (pinfunction "2_2") (pintype "passive"))
      (node (ref "C1") (pin "2") (pintype "passive"))
      (node (ref "C10") (pin "2") (pintype "passive"))
      (node (ref "C11") (pin "2") (pintype "passive"))
      (node (ref "C12") (pin "2") (pintype "passive"))
      (node (ref "C13") (pin "1") (pintype "passive"))
      (node (ref "C14") (pin "1") (pintype "passive"))
      (node (ref "C15") (pin "1") (pintype "passive"))
      (node (ref "C16") (pin "1") (pintype "passive"))
      (node (ref "C17") (pin "1") (pintype "passive"))
      (node (ref "C18") (pin "1") (pintype "passive"))
      (node (ref "C2") (pin "2") (pintype "passive"))
      (node (ref "C25") (pin "2") (pintype "passive"))
      (node (ref "C26") (pin "2") (pintype "passive"))
      (node (ref "C27") (pin "2") (pintype "passive"))
      (node (ref "C28") (pin "2") (pintype "passive"))
      (node (ref "C29") (pin "1") (pintype "passive"))
      (node (ref "C3") (pin "2") (pintype "passive"))
      (node (ref "C30") (pin "2") (pintype "passive"))
      (node (ref "C31") (pin "1") (pintype "passive"))
      (node (ref "C32") (pin "1") (pintype "passive"))
      (node (ref "C33") (pin "2") (pintype "passive"))
      (node (ref "C34") (pin "1") (pintype "passive"))
      (node (ref "C35") (pin "1") (pintype "passive"))
      (node (ref "C4") (pin "2") (pintype "passive"))
      (node (ref "C46") (pin "1") (pintype "passive"))
      (node (ref "C47") (pin "1") (pintype "passive"))
      (node (ref "C48") (pin "1") (pintype "passive"))
      (node (ref "C5") (pin "2") (pintype "passive"))
      (node (ref "C6") (pin "2") (pinfunction "2_2") (pintype "passive"))
      (node (ref "C7") (pin "1") (pintype "passive"))
      (node (ref "C8") (pin "1") (pintype "passive"))
      (node (ref "C9") (pin "2") (pintype "passive"))
      (node (ref "D1") (pin "2") (pinfunction "A_2") (pintype "passive"))
      (node (ref "D4") (pin "1") (pinfunction "1_1") (pintype "passive"))
      (node (ref "DW1") (pin "A") (pintype "passive"))
      (node (ref "DW3") (pin "A") (pintype "passive"))
      (node (ref "DW5") (pin "A") (pintype "passive"))
      (node (ref "J1") (pin "6") (pinfunction "6_6") (pintype "passive"))
      (node (ref "J12") (pin "1") (pinfunction "1_1") (pintype "passive"))
      (node (ref "J2") (pin "6") (pinfunction "6_6") (pintype "passive"))
      (node (ref "J3") (pin "4") (pinfunction "4_4") (pintype "passive"))
      (node (ref "J6") (pin "4") (pinfunction "DC/-_4") (pintype "passive"))
      (node (ref "Q1") (pin "2") (pintype "passive"))
      (node (ref "Q2") (pin "2") (pintype "passive"))
      (node (ref "Q3") (pin "2") (pintype "passive"))
      (node (ref "Q4") (pin "2") (pintype "passive"))
      (node (ref "Q6") (pin "2") (pintype "passive"))
      (node (ref "R16") (pin "1") (pintype "passive"))
      (node (ref "R18") (pin "1") (pintype "passive"))
      (node (ref "R22") (pin "1") (pintype "passive"))
      (node (ref "R23") (pin "1") (pintype "passive"))
      (node (ref "R24") (pin "1") (pintype "passive"))
      (node (ref "R25") (pin "2") (pintype "passive"))
      (node (ref "R31") (pin "1") (pintype "passive"))
      (node (ref "R4") (pin "1") (pintype "passive"))
      (node (ref "R46") (pin "1") (pintype "passive"))
      (node (ref "R5") (pin "1") (pintype "passive"))
      (node (ref "R6") (pin "1") (pintype "passive"))
      (node (ref "RF1") (pin "2") (pinfunction "GND_2") (pintype "passive"))
      (node (ref "RF1") (pin "3") (pinfunction "GND_3") (pintype "passive"))
      (node (ref "U1") (pin "23") (pinfunction "VSS_1_23") (pintype "power_in"))
      (node (ref "U1") (pin "35") (pinfunction "VSS_2_35") (pintype "power_in"))
      (node (ref "U1") (pin "47") (pinfunction "VSS_3_47") (pintype "power_in"))
      (node (ref "U1") (pin "8") (pinfunction "VSSA_8") (pintype "power_in"))
      (node (ref "U2") (pin "11") (pinfunction "GND_11") (pintype "passive"))
      (node (ref "U3") (pin "1") (pinfunction "GND_1") (pintype "passive"))
      (node (ref "U3") (pin "27") (pinfunction "GND_27") (pintype "passive"))
      (node (ref "U3") (pin "34") (pinfunction "GND_34") (pintype "passive"))
      (node (ref "U3") (pin "36") (pinfunction "GND_36") (pintype "passive"))
      (node (ref "U3") (pin "37") (pinfunction "GND_37") (pintype "passive"))
      (node (ref "U3") (pin "40") (pinfunction "GND_40") (pintype "passive"))
      (node (ref "U3") (pin "41") (pinfunction "GND_41") (pintype "passive"))
      (node (ref "U4") (pin "1") (pinfunction "GND_1") (pintype "passive"))
      (node (ref "U5") (pin "7") (pinfunction "GND_7") (pintype "passive"))
      (node (ref "U8") (pin "5") (pinfunction "GND_5") (pintype "passive"))
      (node (ref "X1") (pin "2") (pinfunction "GND_2") (pintype "passive"))
      (node (ref "X1") (pin "4") (pinfunction "GND_4") (pintype "passive"))
    )
    (net (code "58") (name "Net-(C35-Pad2)") (class "Default")
      (node (ref "C35") (pin "2") (pintype "passive"))
      (node (ref "R17") (pin "1") (pintype "passive"))
    )
    (net (code "59") (name "Net-(D3-I{slash}O1)") (class "Default")
      (node (ref "C23") (pin "2") (pinfunction "2_2") (pintype "passive"))
      (node (ref "D3") (pin "1") (pinfunction "I/O1_1") (pintype "passive"))
      (node (ref "J5") (pin "5") (pinfunction "CLK_5") (pintype "passive"))
      (node (ref "R11") (pin "2") (pintype "passive"))
    )
    (net (code "60") (name "Net-(D3-I{slash}O3)") (class "Default")
      (node (ref "C21") (pin "2") (pinfunction "2_2") (pintype "passive"))
      (node (ref "D3") (pin "4") (pinfunction "I/O3_4") (pintype "passive"))
      (node (ref "J5") (pin "3") (pinfunction "RST_3") (pintype "passive"))
      (node (ref "R8") (pin "2") (pintype "passive"))
    )
    (net (code "61") (name "Net-(D3-I{slash}O4)") (class "Default")
      (node (ref "C22") (pin "2") (pinfunction "2_2") (pintype "passive"))
      (node (ref "D3") (pin "5") (pinfunction "I/O4_5") (pintype "passive"))
      (node (ref "J5") (pin "6") (pinfunction "IO_6") (pintype "passive"))
      (node (ref "R10") (pin "2") (pintype "passive"))
    )
    (net (code "62") (name "Net-(D4-Pad2)") (class "Default")
      (node (ref "D4") (pin "2") (pinfunction "2_2") (pintype "passive"))
      (node (ref "R13") (pin "2") (pintype "passive"))
    )
    (net (code "63") (name "Net-(D5-Pad1)") (class "Default")
      (node (ref "D5") (pin "1") (pinfunction "1_1") (pintype "passive"))
      (node (ref "Q3") (pin "3") (pintype "passive"))
    )
    (net (code "64") (name "Net-(D5-Pad2)") (class "Default")
      (node (ref "D5") (pin "2") (pinfunction "2_2") (pintype "passive"))
      (node (ref "R12") (pin "1") (pintype "passive"))
    )
    (net (code "65") (name "Net-(DW4-PadA)") (class "Default")
      (node (ref "DW4") (pin "A") (pintype "passive"))
      (node (ref "Q6") (pin "3") (pintype "passive"))
      (node (ref "RL1") (pin "1") (pinfunction "1_1") (pintype "passive"))
    )
    (net (code "66") (name "Net-(L3-Pad1)") (class "Default")
      (node (ref "L3") (pin "1") (pinfunction "1_1") (pintype "passive"))
      (node (ref "R27") (pin "2") (pintype "passive"))
      (node (ref "R29") (pin "2") (pintype "passive"))
    )
    (net (code "67") (name "Net-(L3-Pad2)") (class "Default")
      (node (ref "L3") (pin "2") (pinfunction "2_2") (pintype "passive"))
      (node (ref "R29") (pin "1") (pintype "passive"))
      (node (ref "R32") (pin "2") (pintype "passive"))
    )
    (net (code "68") (name "Net-(L4-Pad2)") (class "Default")
      (node (ref "L4") (pin "2") (pinfunction "2_2") (pintype "passive"))
      (node (ref "R39") (pin "1") (pintype "passive"))
    )
    (net (code "69") (name "Net-(L4-Pad3)") (class "Default")
      (node (ref "L4") (pin "3") (pinfunction "3_3") (pintype "passive"))
      (node (ref "R42") (pin "1") (pintype "passive"))
      (node (ref "R44") (pin "2") (pintype "passive"))
    )
    (net (code "70") (name "Net-(L4-Pad4)") (class "Default")
      (node (ref "L4") (pin "4") (pinfunction "4_4") (pintype "passive"))
      (node (ref "R40") (pin "2") (pintype "passive"))
      (node (ref "R42") (pin "2") (pintype "passive"))
    )
    (net (code "71") (name "Net-(LED1---Pad1)") (class "Default")
      (node (ref "LED1") (pin "1") (pinfunction "-_1") (pintype "passive"))
      (node (ref "R1") (pin "1") (pintype "passive"))
    )
    (net (code "72") (name "Net-(LED1---Pad3)") (class "Default")
      (node (ref "LED1") (pin "3") (pinfunction "-_3") (pintype "passive"))
      (node (ref "R2") (pin "1") (pintype "passive"))
    )
    (net (code "73") (name "Net-(LED1---Pad4)") (class "Default")
      (node (ref "LED1") (pin "4") (pinfunction "-_4") (pintype "passive"))
      (node (ref "R3") (pin "1") (pintype "passive"))
    )
    (net (code "74") (name "Net-(Q1-Pad1)") (class "Default")
      (node (ref "Q1") (pin "1") (pinfunction "1_1") (pintype "passive"))
      (node (ref "R19") (pin "2") (pintype "passive"))
      (node (ref "R22") (pin "2") (pintype "passive"))
    )
    (net (code "75") (name "Net-(Q2-Pad1)") (class "Default")
      (node (ref "Q2") (pin "1") (pinfunction "1_1") (pintype "passive"))
      (node (ref "R20") (pin "2") (pintype "passive"))
      (node (ref "R23") (pin "2") (pintype "passive"))
    )
    (net (code "76") (name "Net-(Q3-Pad1)") (class "Default")
      (node (ref "Q3") (pin "1") (pinfunction "1_1") (pintype "passive"))
      (node (ref "R21") (pin "2") (pintype "passive"))
      (node (ref "R24") (pin "2") (pintype "passive"))
    )
    (net (code "77") (name "Net-(Q4-Pad1)") (class "Default")
      (node (ref "Q4") (pin "1") (pinfunction "1_1") (pintype "passive"))
      (node (ref "R30") (pin "1") (pintype "passive"))
      (node (ref "R31") (pin "2") (pintype "passive"))
    )
    (net (code "78") (name "Net-(Q5-Pad1)") (class "Default")
      (node (ref "Q5") (pin "1") (pinfunction "1_1") (pintype "passive"))
      (node (ref "R33") (pin "2") (pintype "passive"))
    )
    (net (code "79") (name "Net-(Q6-Pad1)") (class "Default")
      (node (ref "Q6") (pin "1") (pinfunction "1_1") (pintype "passive"))
      (node (ref "R45") (pin "2") (pintype "passive"))
      (node (ref "R46") (pin "2") (pintype "passive"))
    )
    (net (code "80") (name "Net-(R35-Pad1)") (class "Default")
      (node (ref "R35") (pin "1") (pintype "passive"))
      (node (ref "R36") (pin "2") (pintype "passive"))
    )
    (net (code "81") (name "Net-(R36-Pad1)") (class "Default")
      (node (ref "R36") (pin "1") (pintype "passive"))
      (node (ref "R37") (pin "2") (pintype "passive"))
    )
    (net (code "82") (name "Net-(R37-Pad1)") (class "Default")
      (node (ref "R37") (pin "1") (pintype "passive"))
      (node (ref "R38") (pin "2") (pintype "passive"))
    )
    (net (code "83") (name "Net-(R38-Pad1)") (class "Default")
      (node (ref "R38") (pin "1") (pintype "passive"))
      (node (ref "R39") (pin "2") (pintype "passive"))
    )
    (net (code "84") (name "Net-(RF1-SIG)") (class "Default")
      (node (ref "C10") (pin "1") (pintype "passive"))
      (node (ref "R7") (pin "1") (pintype "passive"))
      (node (ref "RF1") (pin "1") (pinfunction "SIG_1") (pintype "passive"))
    )
    (net (code "85") (name "Net-(U1A-VBAT)") (class "Default")
      (node (ref "D2") (pin "3") (pinfunction "3_3") (pintype "passive"))
      (node (ref "U1") (pin "1") (pinfunction "VBAT_1") (pintype "power_in"))
    )
    (net (code "86") (name "Net-(U1A-VDDA)") (class "Default")
      (node (ref "L1") (pin "1") (pinfunction "1_1") (pintype "passive"))
      (node (ref "U1") (pin "9") (pinfunction "VDDA_9") (pintype "power_in"))
    )
    (net (code "87") (name "Net-(U1B-BOOT0)") (class "Default")
      (node (ref "R6") (pin "2") (pintype "passive"))
      (node (ref "U1") (pin "44") (pinfunction "BOOT0_44") (pintype "passive"))
    )
    (net (code "88") (name "Net-(U2-A8)") (class "Default")
      (node (ref "R4") (pin "2") (pintype "passive"))
      (node (ref "U2") (pin "9") (pinfunction "A8_9") (pintype "passive"))
    )
    (net (code "89") (name "Net-(U2-B3)") (class "Default")
      (node (ref "J2") (pin "4") (pinfunction "4_4") (pintype "passive"))
      (node (ref "U2") (pin "17") (pinfunction "B3_17") (pintype "passive"))
    )
    (net (code "90") (name "Net-(U2-B4)") (class "Default")
      (node (ref "J2") (pin "5") (pinfunction "5_5") (pintype "passive"))
      (node (ref "U2") (pin "16") (pinfunction "B4_16") (pintype "passive"))
    )
    (net (code "91") (name "Net-(U2-B8)") (class "Default")
      (node (ref "R5") (pin "2") (pintype "passive"))
      (node (ref "U2") (pin "12") (pinfunction "B8_12") (pintype "passive"))
    )
    (net (code "92") (name "Net-(U3A-RF_ANT)") (class "Default")
      (node (ref "C9") (pin "1") (pintype "passive"))
      (node (ref "R7") (pin "2") (pintype "passive"))
      (node (ref "U3") (pin "35") (pinfunction "RF_ANT_35") (pintype "passive"))
    )
    (net (code "93") (name "Net-(U5-BOOT)") (class "Default")
      (node (ref "C24") (pin "1") (pintype "passive"))
      (node (ref "U5") (pin "1") (pinfunction "BOOT_1") (pintype "passive"))
    )
    (net (code "94") (name "Net-(U5-COMP)") (class "Default")
      (node (ref "C34") (pin "2") (pintype "passive"))
      (node (ref "R17") (pin "2") (pintype "passive"))
      (node (ref "U5") (pin "6") (pinfunction "COMP_6") (pintype "passive"))
    )
    (net (code "95") (name "Net-(U5-EN)") (class "Default")
      (node (ref "R14") (pin "1") (pintype "passive"))
      (node (ref "U5") (pin "3") (pinfunction "EN_3") (pintype "passive"))
    )
    (net (code "96") (name "Net-(U5-PH)") (class "Default")
      (node (ref "C24") (pin "2") (pintype "passive"))
      (node (ref "DW1") (pin "K") (pintype "passive"))
      (node (ref "L2") (pin "1") (pintype "passive"))
      (node (ref "U5") (pin "8") (pinfunction "PH_8") (pintype "passive"))
    )
    (net (code "97") (name "Net-(U5-SS)") (class "Default")
      (node (ref "R16") (pin "2") (pintype "passive"))
      (node (ref "U5") (pin "4") (pinfunction "SS_4") (pintype "passive"))
    )
    (net (code "98") (name "Net-(U5-VSENSE)") (class "Default")
      (node (ref "R15") (pin "1") (pintype "passive"))
      (node (ref "R18") (pin "2") (pintype "passive"))
      (node (ref "U5") (pin "5") (pinfunction "VSENSE_5") (pintype "passive"))
    )
    (net (code "99") (name "Net-(U7-CF)") (class "Default")
      (node (ref "R41") (pin "1") (pintype "passive"))
      (node (ref "U7") (pin "9") (pinfunction "CF_9") (pintype "passive"))
    )
    (net (code "100") (name "Net-(U7-VREF)") (class "Default")
      (node (ref "C41") (pin "2") (pintype "passive"))
      (node (ref "U7") (pin "6") (pinfunction "VREF_6") (pintype "passive"))
    )
    (net (code "101") (name "Net-(U8-SEL)") (class "Default")
      (node (ref "R47") (pin "1") (pintype "passive"))
      (node (ref "U8") (pin "7") (pinfunction "SEL_7") (pintype "passive"))
    )
    (net (code "102") (name "Net-(U8-V5V)") (class "Default")
      (node (ref "C46") (pin "2") (pintype "passive"))
      (node (ref "R47") (pin "2") (pintype "passive"))
      (node (ref "U8") (pin "8") (pinfunction "V5V_8") (pintype "passive"))
    )
    (net (code "103") (name "SIM_GND") (class "Default")
      (node (ref "C19") (pin "1") (pintype "passive"))
      (node (ref "C20") (pin "1") (pinfunction "1_1") (pintype "passive"))
      (node (ref "C21") (pin "1") (pinfunction "1_1") (pintype "passive"))
      (node (ref "C22") (pin "1") (pinfunction "1_1") (pintype "passive"))
      (node (ref "C23") (pin "1") (pinfunction "1_1") (pintype "passive"))
      (node (ref "D3") (pin "2") (pinfunction "GND_2") (pintype "passive"))
      (node (ref "J5") (pin "2") (pinfunction "GND_2") (pintype "passive"))
      (node (ref "J5") (pin "7") (pinfunction "GND_7") (pintype "passive"))
      (node (ref "J5") (pin "8") (pinfunction "GND_8") (pintype "passive"))
      (node (ref "U3") (pin "10") (pinfunction "SIM_GND_10") (pintype "passive"))
    )
    (net (code "104") (name "VBAT") (class "Default")
      (node (ref "B1") (pin "1") (pinfunction "1_1") (pintype "passive"))
      (node (ref "D2") (pin "1") (pinfunction "1_1") (pintype "passive"))
    )
    (net (code "105") (name "unconnected-(J5-VPP-Pad4)") (class "Default")
      (node (ref "J5") (pin "4") (pinfunction "VPP_4") (pintype "passive+no_connect"))
    )
    (net (code "106") (name "unconnected-(M1-Pad1)") (class "Default")
      (node (ref "M1") (pin "1") (pintype "passive"))
    )
    (net (code "107") (name "unconnected-(M2-Pad1)") (class "Default")
      (node (ref "M2") (pin "1") (pintype "passive"))
    )
    (net (code "108") (name "unconnected-(M3-Pad1)") (class "Default")
      (node (ref "M3") (pin "1") (pintype "passive"))
    )
    (net (code "109") (name "unconnected-(RL1-Pad2)") (class "Default")
      (node (ref "RL1") (pin "2") (pinfunction "2_2") (pintype "passive"))
    )
    (net (code "110") (name "unconnected-(RL1-Pad7)") (class "Default")
      (node (ref "RL1") (pin "7") (pinfunction "7_7") (pintype "passive"))
    )
    (net (code "111") (name "unconnected-(U1B-PA0-WKUP-Pad10)") (class "Default")
      (node (ref "U1") (pin "10") (pinfunction "PA0-WKUP_10") (pintype "bidirectional+no_connect"))
    )
    (net (code "112") (name "unconnected-(U1B-PA1-Pad11)") (class "Default")
      (node (ref "U1") (pin "11") (pinfunction "PA1_11") (pintype "bidirectional+no_connect"))
    )
    (net (code "113") (name "unconnected-(U1B-PA6-Pad16)") (class "Default")
      (node (ref "U1") (pin "16") (pinfunction "PA6_16") (pintype "bidirectional+no_connect"))
    )
    (net (code "114") (name "unconnected-(U1B-PA7-Pad17)") (class "Default")
      (node (ref "U1") (pin "17") (pinfunction "PA7_17") (pintype "bidirectional+no_connect"))
    )
    (net (code "115") (name "unconnected-(U1B-PA11-Pad32)") (class "Default")
      (node (ref "U1") (pin "32") (pinfunction "PA11_32") (pintype "bidirectional+no_connect"))
    )
    (net (code "116") (name "unconnected-(U1B-PA12-Pad33)") (class "Default")
      (node (ref "U1") (pin "33") (pinfunction "PA12_33") (pintype "bidirectional+no_connect"))
    )
    (net (code "117") (name "unconnected-(U1B-PB2-Pad20)") (class "Default")
      (node (ref "U1") (pin "20") (pinfunction "PB2_20") (pintype "bidirectional+no_connect"))
    )
    (net (code "118") (name "unconnected-(U1B-PB3-Pad39)") (class "Default")
      (node (ref "U1") (pin "39") (pinfunction "PB3_39") (pintype "bidirectional+no_connect"))
    )
    (net (code "119") (name "unconnected-(U1B-PB4-Pad40)") (class "Default")
      (node (ref "U1") (pin "40") (pinfunction "PB4_40") (pintype "bidirectional"))
    )
    (net (code "120") (name "unconnected-(U1B-PB5-Pad41)") (class "Default")
      (node (ref "U1") (pin "41") (pinfunction "PB5_41") (pintype "bidirectional"))
    )
    (net (code "121") (name "unconnected-(U1B-PB6-Pad42)") (class "Default")
      (node (ref "U1") (pin "42") (pinfunction "PB6_42") (pintype "bidirectional"))
    )
    (net (code "122") (name "unconnected-(U1B-PB8-Pad45)") (class "Default")
      (node (ref "U1") (pin "45") (pinfunction "PB8_45") (pintype "bidirectional+no_connect"))
    )
    (net (code "123") (name "unconnected-(U1B-PB13-Pad26)") (class "Default")
      (node (ref "U1") (pin "26") (pinfunction "PB13_26") (pintype "bidirectional+no_connect"))
    )
    (net (code "124") (name "unconnected-(U1B-PC13-Pad2)") (class "Default")
      (node (ref "U1") (pin "2") (pinfunction "PC13_2") (pintype "bidirectional+no_connect"))
    )
    (net (code "125") (name "unconnected-(U2-A5-Pad6)") (class "Default")
      (node (ref "U2") (pin "6") (pinfunction "A5_6") (pintype "passive+no_connect"))
    )
    (net (code "126") (name "unconnected-(U2-A6-Pad7)") (class "Default")
      (node (ref "U2") (pin "7") (pinfunction "A6_7") (pintype "passive+no_connect"))
    )
    (net (code "127") (name "unconnected-(U2-B5-Pad15)") (class "Default")
      (node (ref "U2") (pin "15") (pinfunction "B5_15") (pintype "passive+no_connect"))
    )
    (net (code "128") (name "unconnected-(U2-B6-Pad14)") (class "Default")
      (node (ref "U2") (pin "14") (pinfunction "B6_14") (pintype "passive+no_connect"))
    )
    (net (code "129") (name "unconnected-(U3A-ADC0-Pad9)") (class "Default")
      (node (ref "U3") (pin "9") (pinfunction "ADC0_9") (pintype "passive+no_connect"))
    )
    (net (code "130") (name "unconnected-(U3A-NC-Pad2)") (class "Default")
      (node (ref "U3") (pin "2") (pinfunction "NC_2") (pintype "passive+no_connect"))
    )
    (net (code "131") (name "unconnected-(U3A-NC-Pad3)") (class "Default")
      (node (ref "U3") (pin "3") (pinfunction "NC_3") (pintype "passive+no_connect"))
    )
    (net (code "132") (name "unconnected-(U3A-NC-Pad4)") (class "Default")
      (node (ref "U3") (pin "4") (pinfunction "NC_4") (pintype "passive+no_connect"))
    )
    (net (code "133") (name "unconnected-(U3A-NC-Pad5)") (class "Default")
      (node (ref "U3") (pin "5") (pinfunction "NC_5") (pintype "passive+no_connect"))
    )
    (net (code "134") (name "unconnected-(U3A-NC-Pad6)") (class "Default")
      (node (ref "U3") (pin "6") (pinfunction "NC_6") (pintype "passive+no_connect"))
    )
    (net (code "135") (name "unconnected-(U3A-NC-Pad8)") (class "Default")
      (node (ref "U3") (pin "8") (pinfunction "NC_8") (pintype "passive+no_connect"))
    )
    (net (code "136") (name "unconnected-(U3A-NC-Pad21)") (class "Default")
      (node (ref "U3") (pin "21") (pinfunction "NC_21") (pintype "passive+no_connect"))
    )
    (net (code "137") (name "unconnected-(U3A-NC-Pad22)") (class "Default")
      (node (ref "U3") (pin "22") (pinfunction "NC_22") (pintype "passive+no_connect"))
    )
    (net (code "138") (name "unconnected-(U3A-NC-Pad23)") (class "Default")
      (node (ref "U3") (pin "23") (pinfunction "NC_23") (pintype "passive+no_connect"))
    )
    (net (code "139") (name "unconnected-(U3A-NC-Pad25)") (class "Default")
      (node (ref "U3") (pin "25") (pinfunction "NC_25") (pintype "passive+no_connect"))
    )
    (net (code "140") (name "unconnected-(U3A-NC-Pad26)") (class "Default")
      (node (ref "U3") (pin "26") (pinfunction "NC_26") (pintype "passive+no_connect"))
    )
    (net (code "141") (name "unconnected-(U3A-NC-Pad30)") (class "Default")
      (node (ref "U3") (pin "30") (pinfunction "NC_30") (pintype "passive+no_connect"))
    )
    (net (code "142") (name "unconnected-(U3A-NC-Pad31)") (class "Default")
      (node (ref "U3") (pin "31") (pinfunction "NC_31") (pintype "passive+no_connect"))
    )
    (net (code "143") (name "unconnected-(U3A-NC-Pad32)") (class "Default")
      (node (ref "U3") (pin "32") (pinfunction "NC_32") (pintype "passive+no_connect"))
    )
    (net (code "144") (name "unconnected-(U3A-NC-Pad33)") (class "Default")
      (node (ref "U3") (pin "33") (pinfunction "NC_33") (pintype "passive+no_connect"))
    )
    (net (code "145") (name "unconnected-(U3A-NC-Pad44)") (class "Default")
      (node (ref "U3") (pin "44") (pinfunction "NC_44") (pintype "passive+no_connect"))
    )
    (net (code "146") (name "unconnected-(U3A-PSM_EINT-Pad19)") (class "Default")
      (node (ref "U3") (pin "19") (pinfunction "PSM_EINT_19") (pintype "passive+no_connect"))
    )
    (net (code "147") (name "unconnected-(U3A-RXD_AUX-Pad28)") (class "Default")
      (node (ref "U3") (pin "28") (pinfunction "RXD_AUX_28") (pintype "passive+no_connect"))
    )
    (net (code "148") (name "unconnected-(U3A-TXD_AUX-Pad29)") (class "Default")
      (node (ref "U3") (pin "29") (pinfunction "TXD_AUX_29") (pintype "passive+no_connect"))
    )
    (net (code "149") (name "unconnected-(U3B-NC-Pad45)") (class "Default")
      (node (ref "U3") (pin "45") (pinfunction "NC_45") (pintype "passive+no_connect"))
    )
    (net (code "150") (name "unconnected-(U3B-NC-Pad46)") (class "Default")
      (node (ref "U3") (pin "46") (pinfunction "NC_46") (pintype "passive+no_connect"))
    )
    (net (code "151") (name "unconnected-(U3B-NC-Pad48)") (class "Default")
      (node (ref "U3") (pin "48") (pinfunction "NC_48") (pintype "passive+no_connect"))
    )
    (net (code "152") (name "unconnected-(U3B-NC-Pad52)") (class "Default")
      (node (ref "U3") (pin "52") (pinfunction "NC_52") (pintype "passive+no_connect"))
    )
    (net (code "153") (name "unconnected-(U3B-NC-Pad53)") (class "Default")
      (node (ref "U3") (pin "53") (pinfunction "NC_53") (pintype "passive+no_connect"))
    )
    (net (code "154") (name "unconnected-(U3B-NC-Pad54)") (class "Default")
      (node (ref "U3") (pin "54") (pinfunction "NC_54") (pintype "passive+no_connect"))
    )
    (net (code "155") (name "unconnected-(U3B-NC-Pad55)") (class "Default")
      (node (ref "U3") (pin "55") (pinfunction "NC_55") (pintype "passive+no_connect"))
    )
    (net (code "156") (name "unconnected-(U3B-NC-Pad56)") (class "Default")
      (node (ref "U3") (pin "56") (pinfunction "NC_56") (pintype "passive+no_connect"))
    )
    (net (code "157") (name "unconnected-(U3B-NC-Pad57)") (class "Default")
      (node (ref "U3") (pin "57") (pinfunction "NC_57") (pintype "passive+no_connect"))
    )
    (net (code "158") (name "unconnected-(U3B-NC-Pad58)") (class "Default")
      (node (ref "U3") (pin "58") (pinfunction "NC_58") (pintype "passive+no_connect"))
    )
    (net (code "159") (name "unconnected-(U3B-USB_DM-Pad51)") (class "Default")
      (node (ref "U3") (pin "51") (pinfunction "USB_DM_51") (pintype "passive+no_connect"))
    )
    (net (code "160") (name "unconnected-(U3B-USB_DP-Pad50)") (class "Default")
      (node (ref "U3") (pin "50") (pinfunction "USB_DP_50") (pintype "passive+no_connect"))
    )
    (net (code "161") (name "unconnected-(U3B-USB_MODE-Pad47)") (class "Default")
      (node (ref "U3") (pin "47") (pinfunction "USB_MODE_47") (pintype "passive+no_connect"))
    )
    (net (code "162") (name "unconnected-(U3B-VUSB_3V3-Pad49)") (class "Default")
      (node (ref "U3") (pin "49") (pinfunction "VUSB_3V3_49") (pintype "passive+no_connect"))
    )
    (net (code "163") (name "unconnected-(U7-IAN-Pad1)") (class "Default")
      (node (ref "U7") (pin "1") (pinfunction "IAN_1") (pintype "passive+no_connect"))
    )
    (net (code "164") (name "unconnected-(U7-IAP-Pad16)") (class "Default")
      (node (ref "U7") (pin "16") (pinfunction "IAP_16") (pintype "passive+no_connect"))
    )
    (net (code "165") (name "unconnected-(U8-NC-Pad1)") (class "Default")
      (node (ref "U8") (pin "1") (pinfunction "NC_1") (pintype "passive+no_connect"))
    )
    (net (code "166") (name "unconnected-(U8-NC-Pad2)") (class "Default")
      (node (ref "U8") (pin "2") (pinfunction "NC_2") (pintype "passive+no_connect"))
    )
  )
)
